# MP2307DN.net
KiCad netlist of a schematic drawn in Altium Designer
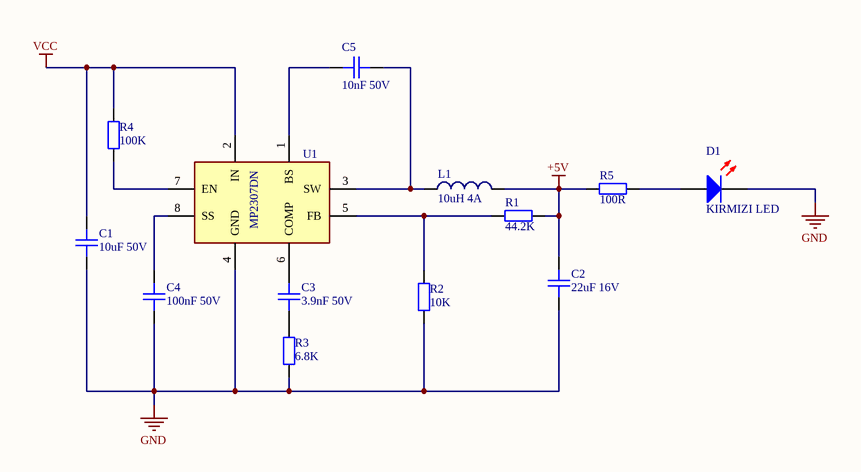
[diagram p0: MP2307DN.SchDoc]

(export (version "E")
  (design (tool "Eeschema 10.0.6"))
  (components
    (comp (ref "C1")
      (value "CAP CER 10UF 50V X5R 1206")
      (footprint "CAP 1206/3216")
      (description "10µF ±10% 50V Ceramic Capacitor X5R 1206 (3216 Metric)")
      (fields (field (name "DEGER") "10uF 50V"))
      (libsource (lib "PROJE") (part "10uF 50V 1206"))
    )
    (comp (ref "C2")
      (value "CAP CERAMIC 22UF 16V X7S 20% PAD")
      (footprint "CAP 1206/3216")
      (description "22µF ±20% 16V Ceramic Capacitor X7S 1206 (3216 Metric)")
      (fields (field (name "DEGER") "22uF 16V"))
      (libsource (lib "PROJE") (part "22uF 16V 1206"))
    )
    (comp (ref "C3")
      (value "CAP CER 3900PF 50V X7R 0805")
      (footprint "CAP 0805/2012")
      (description "3900pF ±10% 50V Ceramic Capacitor X7R 0805 (2012 Metric)")
      (fields (field (name "DEGER") "3.9nF 50V"))
      (libsource (lib "PROJE") (part "3.9nF 50V 0805"))
    )
    (comp (ref "C4")
      (value "CAP CER 0.1UF 50V X7R 0805")
      (footprint "CAP 0805/2012")
      (description "0.1µF ±10% 50V Ceramic Capacitor X7R 0805 (2012 Metric)")
      (fields (field (name "DEGER") "100nF 50V"))
      (libsource (lib "PROJE") (part "100nF 50V 0805"))
    )
    (comp (ref "C5")
      (value "CAP CER 10000PF 50V X7R 0805")
      (footprint "CAP 0805/2012")
      (description "10000pF ±10% 50V Ceramic Capacitor X7R 0805 (2012 Metric)")
      (fields (field (name "DEGER") "10nF 50V"))
      (libsource (lib "PROJE") (part "10nF 50V 0805"))
    )
    (comp (ref "D1")
      (value "Red 645nm LED Indication - Discrete 1.8V 0805")
      (footprint "SMD: LED 0805/2012 RED")
      (description "LED RED DIFFUSED 0805 SMD")
      (fields (field (name "DEGER") "KIRMIZI LED"))
      (libsource (lib "PROJE") (part "LED_Kırmızı"))
    )
    (comp (ref "L1")
      (value "FIXED IND 10UH 4A 68 MOHM SMD")
      (footprint "ASPI-0630LR-100M-T15")
      (description "10µH Shielded Molded Inductor 4A 68mOhm Max Nonstandard")
      (fields (field (name "DEGER") "10uH 4A"))
      (libsource (lib "PROJE") (part "10uH 4A"))
    )
    (comp (ref "R1")
      (value "RES SMD 44.2K OHM 1% 1/8W 0805")
      (footprint "RES_0805")
      (description "44.2 kOhms ±1% 0.125W, 1/8W Chip Resistor 0805 (2012 Metric) Moisture Resistant Thick Film")
      (fields (field (name "DEGER") "44.2K"))
      (libsource (lib "PROJE") (part "44.2K 0805"))
    )
    (comp (ref "R2")
      (value "RES SMD 10K OHM 1% 1/8W 0805")
      (footprint "RES_0805")
      (description "10 kOhms ±1% 0.125W, 1/8W Chip Resistor 0805 (2012 Metric) Moisture Resistant Thick Film")
      (fields (field (name "DEGER") "10K"))
      (libsource (lib "PROJE") (part "10K 0805"))
    )
    (comp (ref "R3")
      (value "RES SMD 6.8K OHM 1% 1/8W 0805")
      (footprint "RES_0805")
      (description "6.8 kOhms ±1% 0.125W, 1/8W Chip Resistor 0805 (2012 Metric) Moisture Resistant Thick Film")
      (fields (field (name "DEGER") "6.8K"))
      (libsource (lib "PROJE") (part "6.8K 0805"))
    )
    (comp (ref "R4")
      (value "RES SMD 100K OHM 1% 1/8W 0805")
      (footprint "RES_0805")
      (description "100 kOhms ±1% 0.125W, 1/8W Chip Resistor 0805 (2012 Metric) Moisture Resistant Thick Film")
      (fields (field (name "DEGER") "100K"))
      (libsource (lib "PROJE") (part "100K 0805"))
    )
    (comp (ref "R5")
      (value "RES SMD 100 OHM 1% 1/8W 0805")
      (footprint "RES_0805")
      (description "100 Ohms ±1% 0.125W, 1/8W Chip Resistor 0805 (2012 Metric) Moisture Resistant Thick Film")
      (fields (field (name "DEGER") "100R"))
      (libsource (lib "PROJE") (part "100R 0805"))
    )
    (comp (ref "U1")
      (value "IC REG BUCK ADJUSTABLE 3A 8SOIC")
      (footprint "SOIC8_PAD")
      (fields (field (name "DEGER") "MP2307DN"))
      (libsource (lib "PROJE") (part "MP2307DN"))
    )
  )
  (nets
    (net (code "1") (name "+5V") (class "Default")
      (node (ref "C2") (pin "2") (pinfunction "2_2") (pintype "passive"))
      (node (ref "L1") (pin "2") (pinfunction "2_2") (pintype "passive"))
      (node (ref "R1") (pin "2") (pinfunction "2_2") (pintype "passive"))
      (node (ref "R5") (pin "1") (pinfunction "1_1") (pintype "passive"))
    )
    (net (code "2") (name "GND") (class "Default")
      (node (ref "C1") (pin "1") (pinfunction "1_1") (pintype "passive"))
      (node (ref "C2") (pin "1") (pinfunction "1_1") (pintype "passive"))
      (node (ref "C4") (pin "1") (pinfunction "1_1") (pintype "passive"))
      (node (ref "D1") (pin "2") (pinfunction "K_2") (pintype "passive"))
      (node (ref "R2") (pin "1") (pinfunction "1_1") (pintype "passive"))
      (node (ref "R3") (pin "1") (pinfunction "1_1") (pintype "passive"))
      (node (ref "U1") (pin "4") (pinfunction "GND_4") (pintype "passive"))
    )
    (net (code "3") (name "Net-(C3-Pad1)") (class "Default")
      (node (ref "C3") (pin "1") (pinfunction "1_1") (pintype "passive"))
      (node (ref "R3") (pin "2") (pinfunction "2_2") (pintype "passive"))
    )
    (net (code "4") (name "Net-(D1-A)") (class "Default")
      (node (ref "D1") (pin "1") (pinfunction "A_1") (pintype "passive"))
      (node (ref "R5") (pin "2") (pinfunction "2_2") (pintype "passive"))
    )
    (net (code "5") (name "Net-(U1-BS)") (class "Default")
      (node (ref "C5") (pin "1") (pinfunction "1_1") (pintype "passive"))
      (node (ref "U1") (pin "1") (pinfunction "BS_1") (pintype "passive"))
    )
    (net (code "6") (name "Net-(U1-COMP)") (class "Default")
      (node (ref "C3") (pin "2") (pinfunction "2_2") (pintype "passive"))
      (node (ref "U1") (pin "6") (pinfunction "COMP_6") (pintype "passive"))
    )
    (net (code "7") (name "Net-(U1-EN)") (class "Default")
      (node (ref "R4") (pin "1") (pinfunction "1_1") (pintype "passive"))
      (node (ref "U1") (pin "7") (pinfunction "EN_7") (pintype "passive"))
    )
    (net (code "8") (name "Net-(U1-FB)") (class "Default")
      (node (ref "R1") (pin "1") (pinfunction "1_1") (pintype "passive"))
      (node (ref "R2") (pin "2") (pinfunction "2_2") (pintype "passive"))
      (node (ref "U1") (pin "5") (pinfunction "FB_5") (pintype "passive"))
    )
    (net (code "9") (name "Net-(U1-SS)") (class "Default")
      (node (ref "C4") (pin "2") (pinfunction "2_2") (pintype "passive"))
      (node (ref "U1") (pin "8") (pinfunction "SS_8") (pintype "passive"))
    )
    (net (code "10") (name "Net-(U1-SW)") (class "Default")
      (node (ref "C5") (pin "2") (pinfunction "2_2") (pintype "passive"))
      (node (ref "L1") (pin "1") (pinfunction "1_1") (pintype "passive"))
      (node (ref "U1") (pin "3") (pinfunction "SW_3") (pintype "passive"))
    )
    (net (code "11") (name "VCC") (class "Default")
      (node (ref "C1") (pin "2") (pinfunction "2_2") (pintype "passive"))
      (node (ref "R4") (pin "2") (pinfunction "2_2") (pintype "passive"))
      (node (ref "U1") (pin "2") (pinfunction "IN_2") (pintype "passive"))
    )
  )
)
